# CanLogger_V2.net
KiCad netlist of a schematic drawn in EAGLE
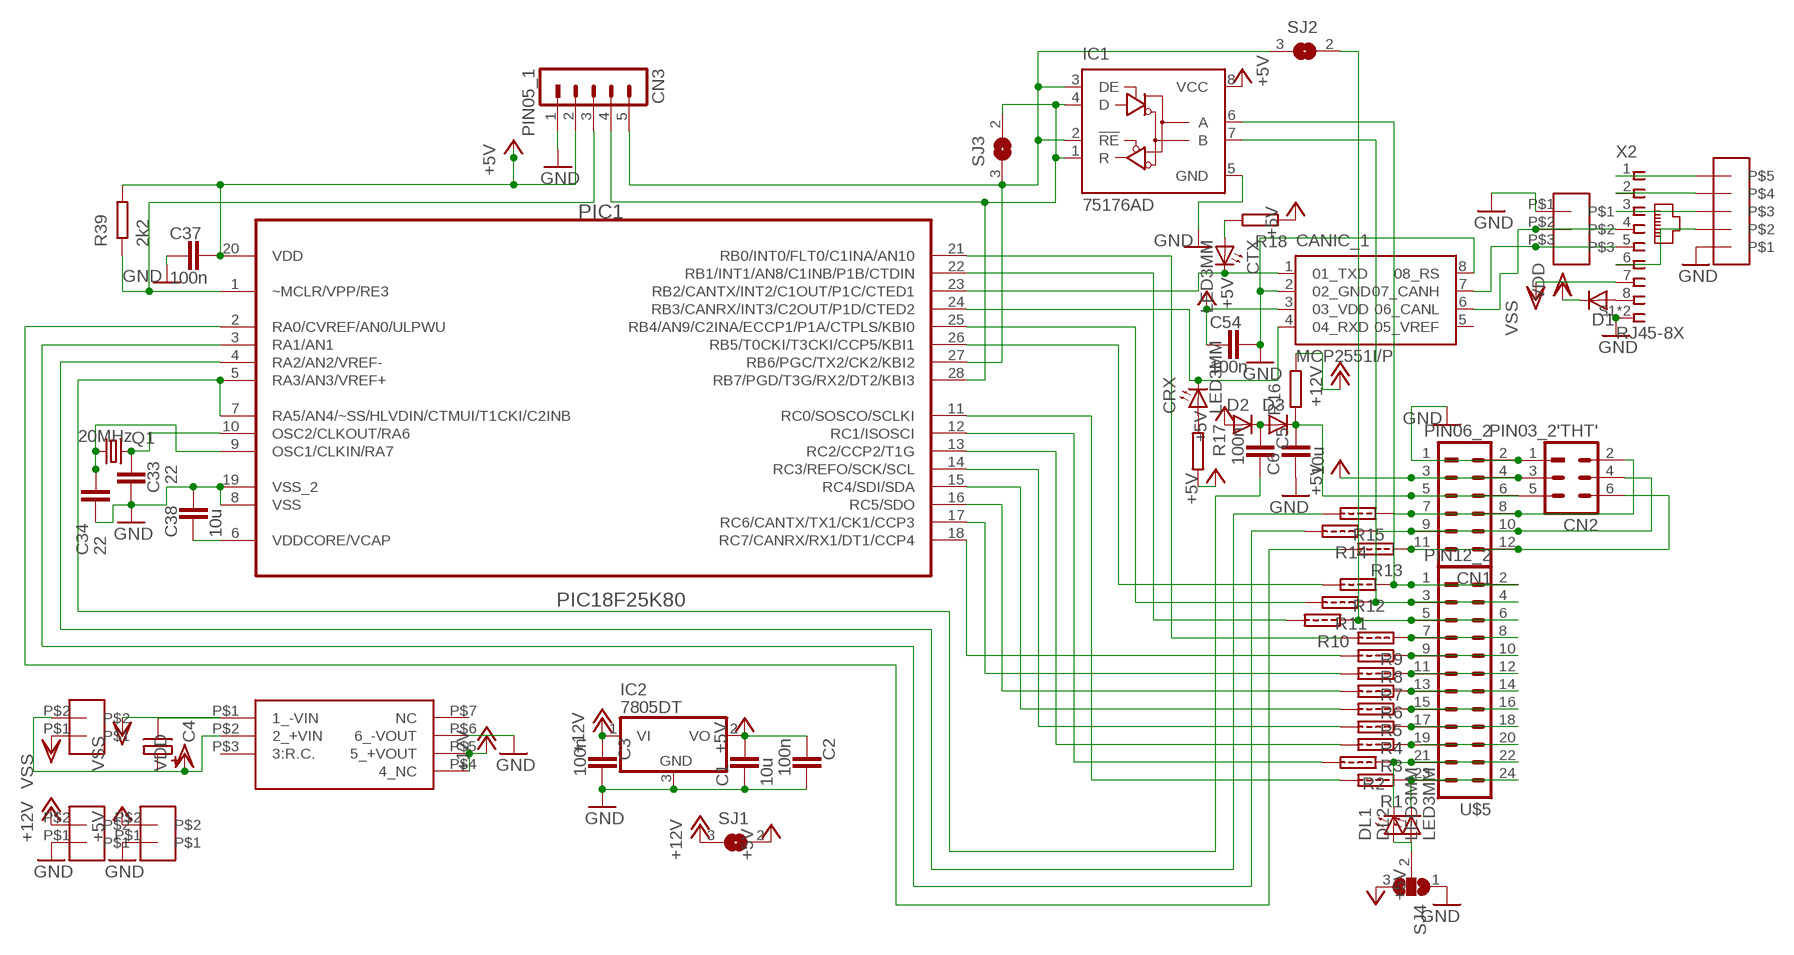
[diagram p0: schematic, sheet 1]

(export (version "E")
  (design (tool "Eeschema 10.0.6"))
  (components
    (comp (ref "C1")
      (value "10u")
      (footprint "eagle-import:R0805")
      (libsource (lib "eagle-import") (part "C0805"))
    )
    (comp (ref "C2")
      (value "100n")
      (footprint "eagle-import:R0805")
      (libsource (lib "eagle-import") (part "C0805"))
    )
    (comp (ref "C3")
      (value "100n")
      (footprint "eagle-import:R0805")
      (libsource (lib "eagle-import") (part "C0805"))
    )
    (comp (ref "C4")
      (value "C_EL1R05")
      (footprint "eagle-import:C_EL1RASZT05")
      (libsource (lib "eagle-import") (part "C_EL1R05"))
    )
    (comp (ref "C5")
      (value "100n")
      (footprint "eagle-import:R0805")
      (libsource (lib "eagle-import") (part "C0805"))
    )
    (comp (ref "C6")
      (value "10u")
      (footprint "eagle-import:R0805")
      (libsource (lib "eagle-import") (part "C0805"))
    )
    (comp (ref "C33")
      (value "22")
      (footprint "eagle-import:R0805")
      (libsource (lib "eagle-import") (part "C0805"))
    )
    (comp (ref "C34")
      (value "22")
      (footprint "eagle-import:R0805")
      (libsource (lib "eagle-import") (part "C0805"))
    )
    (comp (ref "C37")
      (value "100n")
      (footprint "eagle-import:R0805")
      (libsource (lib "eagle-import") (part "C0805"))
    )
    (comp (ref "C38")
      (value "10u")
      (footprint "eagle-import:R0805")
      (libsource (lib "eagle-import") (part "C0805"))
    )
    (comp (ref "C54")
      (value "100n")
      (footprint "eagle-import:R0805")
      (libsource (lib "eagle-import") (part "C0805"))
    )
    (comp (ref "CANIC_1")
      (value "MCP2551I/P")
      (footprint "eagle-import:DIL_8")
      (libsource (lib "eagle-import") (part "MCP2551I/P"))
    )
    (comp (ref "CN1")
      (value "PIN06_2")
      (footprint "eagle-import:PIN06_2")
      (libsource (lib "eagle-import") (part "PIN06_2"))
    )
    (comp (ref "CN2")
      (value "PIN03_2'THT'")
      (footprint "eagle-import:PIN03_2")
      (libsource (lib "eagle-import") (part "PIN03_2'THT'"))
    )
    (comp (ref "CN3")
      (value "PIN05_1")
      (footprint "eagle-import:PIN05_1")
      (libsource (lib "eagle-import") (part "PIN05_1"))
    )
    (comp (ref "CN_CAN")
      (value "FEHER_TUS_3")
      (footprint "eagle-import:FEHER_TUS_3")
      (libsource (lib "eagle-import") (part "FEHER_TUS_3"))
    )
    (comp (ref "CRX")
      (value "LED3MM")
      (footprint "eagle-import:LED3MM")
      (libsource (lib "eagle-import") (part "LED3MM"))
    )
    (comp (ref "CTX")
      (value "LED3MM")
      (footprint "eagle-import:LED3MM")
      (libsource (lib "eagle-import") (part "LED3MM"))
    )
    (comp (ref "D1")
      (value "D1R")
      (footprint "eagle-import:D1RASZT")
      (libsource (lib "eagle-import") (part "D1R"))
    )
    (comp (ref "D2")
      (value "D0805")
      (footprint "eagle-import:D0805")
      (libsource (lib "eagle-import") (part "D0805"))
    )
    (comp (ref "D3")
      (value "D0805")
      (footprint "eagle-import:D0805")
      (libsource (lib "eagle-import") (part "D0805"))
    )
    (comp (ref "DL1")
      (value "LED3MM")
      (footprint "eagle-import:LED3MM")
      (libsource (lib "eagle-import") (part "LED3MM"))
    )
    (comp (ref "DL2")
      (value "LED3MM")
      (footprint "eagle-import:LED3MM")
      (libsource (lib "eagle-import") (part "LED3MM"))
    )
    (comp (ref "IC1")
      (value "75176AD")
      (footprint "eagle-import:D_R-PDSO-G8")
      (libsource (lib "eagle-import") (part "75176AD"))
    )
    (comp (ref "IC2")
      (value "7805DT")
      (footprint "eagle-import:TO252")
      (libsource (lib "eagle-import") (part "78DT05"))
    )
    (comp (ref "PIC1")
      (value "PIC18F25K80")
      (footprint "eagle-import:SOIC127P1030X265-28N")
      (libsource (lib "eagle-import") (part "PIC18F25K80"))
    )
    (comp (ref "Q1")
      (value "20MHz")
      (footprint "eagle-import:XTAL_QS")
      (libsource (lib "eagle-import") (part "XTAL_2QS"))
    )
    (comp (ref "R1")
      (value "RNULL_EU0805")
      (footprint "eagle-import:R0805_C")
      (libsource (lib "eagle-import") (part "RNULL_EU0805"))
    )
    (comp (ref "R2")
      (value "RNULL_EU0805")
      (footprint "eagle-import:R0805_C")
      (libsource (lib "eagle-import") (part "RNULL_EU0805"))
    )
    (comp (ref "R3")
      (value "RNULL_EU0805")
      (footprint "eagle-import:R0805_C")
      (libsource (lib "eagle-import") (part "RNULL_EU0805"))
    )
    (comp (ref "R4")
      (value "RNULL_EU0805")
      (footprint "eagle-import:R0805_C")
      (libsource (lib "eagle-import") (part "RNULL_EU0805"))
    )
    (comp (ref "R5")
      (value "RNULL_EU0805")
      (footprint "eagle-import:R0805_C")
      (libsource (lib "eagle-import") (part "RNULL_EU0805"))
    )
    (comp (ref "R6")
      (value "RNULL_EU0805")
      (footprint "eagle-import:R0805_C")
      (libsource (lib "eagle-import") (part "RNULL_EU0805"))
    )
    (comp (ref "R7")
      (value "RNULL_EU0805")
      (footprint "eagle-import:R0805_C")
      (libsource (lib "eagle-import") (part "RNULL_EU0805"))
    )
    (comp (ref "R8")
      (value "RNULL_EU0805")
      (footprint "eagle-import:R0805_C")
      (libsource (lib "eagle-import") (part "RNULL_EU0805"))
    )
    (comp (ref "R9")
      (value "RNULL_EU0805")
      (footprint "eagle-import:R0805_C")
      (libsource (lib "eagle-import") (part "RNULL_EU0805"))
    )
    (comp (ref "R10")
      (value "RNULL_EU0805")
      (footprint "eagle-import:R0805_C")
      (libsource (lib "eagle-import") (part "RNULL_EU0805"))
    )
    (comp (ref "R11")
      (value "RNULL_EU0805")
      (footprint "eagle-import:R0805_C")
      (libsource (lib "eagle-import") (part "RNULL_EU0805"))
    )
    (comp (ref "R12")
      (value "RNULL_EU0805")
      (footprint "eagle-import:R0805_C")
      (libsource (lib "eagle-import") (part "RNULL_EU0805"))
    )
    (comp (ref "R13")
      (value "RNULL_EU0805")
      (footprint "eagle-import:R0805_C")
      (libsource (lib "eagle-import") (part "RNULL_EU0805"))
    )
    (comp (ref "R14")
      (value "RNULL_EU0805")
      (footprint "eagle-import:R0805_C")
      (libsource (lib "eagle-import") (part "RNULL_EU0805"))
    )
    (comp (ref "R15")
      (value "RNULL_EU0805")
      (footprint "eagle-import:R0805_C")
      (libsource (lib "eagle-import") (part "RNULL_EU0805"))
    )
    (comp (ref "R16")
      (value "R_EU0805")
      (footprint "eagle-import:R0805")
      (libsource (lib "eagle-import") (part "R_EU0805"))
    )
    (comp (ref "R17")
      (value "R_EU0805")
      (footprint "eagle-import:R0805")
      (libsource (lib "eagle-import") (part "R_EU0805"))
    )
    (comp (ref "R18")
      (value "R_EU0805")
      (footprint "eagle-import:R0805")
      (libsource (lib "eagle-import") (part "R_EU0805"))
    )
    (comp (ref "R39")
      (value "2k2")
      (footprint "eagle-import:R0805")
      (libsource (lib "eagle-import") (part "R_EU0805"))
    )
    (comp (ref "SJ1") (value "SJ") (footprint "eagle-import:SJ") (libsource (lib "eagle-import") (part "SJ")))
    (comp (ref "SJ2") (value "SJ") (footprint "eagle-import:SJ") (libsource (lib "eagle-import") (part "SJ")))
    (comp (ref "SJ3") (value "SJ") (footprint "eagle-import:SJ") (libsource (lib "eagle-import") (part "SJ")))
    (comp (ref "SJ4")
      (value "SJ2W")
      (footprint "eagle-import:SJ2")
      (libsource (lib "eagle-import") (part "SJ2W"))
    )
    (comp (ref "U$1")
      (value "FEHER_TUS_5")
      (footprint "eagle-import:FEHER_TUS_5")
      (libsource (lib "eagle-import") (part "FEHER_TUS_5"))
    )
    (comp (ref "U$2")
      (value "FEHER_TUS_2ALLO")
      (footprint "eagle-import:FEHER_TUS_2")
      (libsource (lib "eagle-import") (part "FEHER_TUS_2ALLO"))
    )
    (comp (ref "U$3")
      (value "FEHER_TUS_2ALLO")
      (footprint "eagle-import:FEHER_TUS_2")
      (libsource (lib "eagle-import") (part "FEHER_TUS_2ALLO"))
    )
    (comp (ref "U$4")
      (value "FEHER_TUS_2ALLO")
      (footprint "eagle-import:FEHER_TUS_2")
      (libsource (lib "eagle-import") (part "FEHER_TUS_2ALLO"))
    )
    (comp (ref "U$5")
      (value "PIN12_2")
      (footprint "eagle-import:PIN12_2")
      (libsource (lib "eagle-import") (part "PIN12_2"))
    )
    (comp (ref "U$6")
      (value "SPA02C")
      (footprint "eagle-import:SPA02C")
      (libsource (lib "eagle-import") (part "SPA02C"))
    )
    (comp (ref "X2")
      (value "RJ45-8X")
      (footprint "eagle-import:RJ45")
      (libsource (lib "eagle-import") (part "RJ45-8X"))
    )
  )
  (nets
    (net (code "1") (name "+5V") (class "Default")
      (node (ref "C1") (pin "1") (pinfunction "1_1") (pintype "passive"))
      (node (ref "C2") (pin "2") (pinfunction "2_2") (pintype "passive"))
      (node (ref "C37") (pin "1") (pinfunction "1_1") (pintype "passive"))
      (node (ref "C54") (pin "2") (pinfunction "2_2") (pintype "passive"))
      (node (ref "CANIC_1") (pin "3") (pinfunction "03_VDD_3") (pintype "power_in"))
      (node (ref "CN1") (pin "3") (pinfunction "3_3") (pintype "passive"))
      (node (ref "CN1") (pin "4") (pinfunction "4_4") (pintype "passive"))
      (node (ref "CN2") (pin "3") (pinfunction "3_3") (pintype "passive"))
      (node (ref "CN3") (pin "2") (pinfunction "2_2") (pintype "passive"))
      (node (ref "D2") (pin "1") (pinfunction "A_1") (pintype "passive"))
      (node (ref "IC1") (pin "8") (pinfunction "VCC_8") (pintype "power_in"))
      (node (ref "IC2") (pin "2") (pinfunction "VO_2") (pintype "passive"))
      (node (ref "PIC1") (pin "20") (pinfunction "VDD_20") (pintype "power_in"))
      (node (ref "R17") (pin "2") (pinfunction "E_2") (pintype "passive"))
      (node (ref "R18") (pin "1") (pinfunction "A_1") (pintype "passive"))
      (node (ref "R39") (pin "2") (pinfunction "E_2") (pintype "passive"))
      (node (ref "SJ1") (pin "2") (pinfunction "2_2") (pintype "passive"))
      (node (ref "SJ4") (pin "3") (pinfunction "3_3") (pintype "passive"))
      (node (ref "U$4") (pin "P$2") (pinfunction "P$2_P$2") (pintype "bidirectional"))
    )
    (net (code "2") (name "+12V") (class "Default")
      (node (ref "C3") (pin "2") (pinfunction "2_2") (pintype "passive"))
      (node (ref "IC2") (pin "1") (pinfunction "VI_1") (pintype "input"))
      (node (ref "R16") (pin "2") (pinfunction "E_2") (pintype "passive"))
      (node (ref "SJ1") (pin "3") (pinfunction "1_3") (pintype "passive"))
      (node (ref "U$3") (pin "P$2") (pinfunction "P$2_P$2") (pintype "bidirectional"))
      (node (ref "U$6") (pin "P$4") (pinfunction "4_NC_P$4") (pintype "bidirectional"))
      (node (ref "U$6") (pin "P$5") (pinfunction "5_+VOUT_P$5") (pintype "bidirectional"))
    )
    (net (code "3") (name "GND") (class "Default")
      (node (ref "C1") (pin "2") (pinfunction "2_2") (pintype "passive"))
      (node (ref "C2") (pin "1") (pinfunction "1_1") (pintype "passive"))
      (node (ref "C3") (pin "1") (pinfunction "1_1") (pintype "passive"))
      (node (ref "C33") (pin "2") (pinfunction "2_2") (pintype "passive"))
      (node (ref "C34") (pin "2") (pinfunction "2_2") (pintype "passive"))
      (node (ref "C37") (pin "2") (pinfunction "2_2") (pintype "passive"))
      (node (ref "C38") (pin "1") (pinfunction "1_1") (pintype "passive"))
      (node (ref "C54") (pin "1") (pinfunction "1_1") (pintype "passive"))
      (node (ref "C6") (pin "2") (pinfunction "2_2") (pintype "passive"))
      (node (ref "CANIC_1") (pin "2") (pinfunction "02_GND_2") (pintype "power_in"))
      (node (ref "CANIC_1") (pin "8") (pinfunction "08_RS_8") (pintype "input"))
      (node (ref "CN1") (pin "1") (pinfunction "1_1") (pintype "passive"))
      (node (ref "CN1") (pin "2") (pinfunction "2_2") (pintype "passive"))
      (node (ref "CN2") (pin "1") (pinfunction "1_1") (pintype "passive"))
      (node (ref "CN3") (pin "1") (pinfunction "1_1") (pintype "passive"))
      (node (ref "CN_CAN") (pin "P$1") (pinfunction "P$1_P$1") (pintype "bidirectional"))
      (node (ref "IC1") (pin "5") (pinfunction "GND_5") (pintype "power_in"))
      (node (ref "IC2") (pin "3") (pinfunction "GND_3") (pintype "passive"))
      (node (ref "PIC1") (pin "19") (pinfunction "VSS_2_19") (pintype "power_in"))
      (node (ref "PIC1") (pin "8") (pinfunction "VSS_8") (pintype "power_in"))
      (node (ref "SJ4") (pin "1") (pinfunction "1_1") (pintype "passive"))
      (node (ref "U$1") (pin "P$1") (pinfunction "P$1_P$1") (pintype "bidirectional"))
      (node (ref "U$3") (pin "P$1") (pinfunction "P$1_P$1") (pintype "bidirectional"))
      (node (ref "U$4") (pin "P$1") (pinfunction "P$1_P$1") (pintype "bidirectional"))
      (node (ref "U$6") (pin "P$6") (pinfunction "6_-VOUT_P$6") (pintype "bidirectional"))
      (node (ref "X2") (pin "S1") (pinfunction "S_S1") (pintype "passive"))
      (node (ref "X2") (pin "S2") (pinfunction "S_S2") (pintype "passive"))
    )
    (net (code "4") (name "Net-(CANIC_1-01_TXD)") (class "Default")
      (node (ref "CANIC_1") (pin "1") (pinfunction "01_TXD_1") (pintype "input"))
      (node (ref "CTX") (pin "K") (pinfunction "C_K") (pintype "passive"))
      (node (ref "PIC1") (pin "23") (pinfunction "RB2/CANTX/INT2/C1OUT/P1C/CTED1_23") (pintype "bidirectional"))
    )
    (net (code "5") (name "Net-(CANIC_1-04_RXD)") (class "Default")
      (node (ref "CANIC_1") (pin "4") (pinfunction "04_RXD_4") (pintype "output"))
      (node (ref "CRX") (pin "K") (pinfunction "C_K") (pintype "passive"))
      (node (ref "PIC1") (pin "24") (pinfunction "RB3/CANRX/INT3/C2OUT/P1D/CTED2_24") (pintype "bidirectional"))
    )
    (net (code "6") (name "Net-(CANIC_1-06_CANL)") (class "Default")
      (node (ref "CANIC_1") (pin "6") (pinfunction "06_CANL_6") (pintype "bidirectional"))
      (node (ref "CN_CAN") (pin "P$2") (pinfunction "P$2_P$2") (pintype "bidirectional"))
      (node (ref "X2") (pin "4") (pinfunction "4_4") (pintype "passive"))
    )
    (net (code "7") (name "Net-(CANIC_1-07_CANH)") (class "Default")
      (node (ref "CANIC_1") (pin "7") (pinfunction "07_CANH_7") (pintype "bidirectional"))
      (node (ref "CN_CAN") (pin "P$3") (pinfunction "P$3_P$3") (pintype "bidirectional"))
      (node (ref "X2") (pin "5") (pinfunction "5_5") (pintype "passive"))
    )
    (net (code "8") (name "Net-(D1-A)") (class "Default")
      (node (ref "D1") (pin "P$1") (pinfunction "A_P$1") (pintype "passive"))
      (node (ref "X2") (pin "8") (pinfunction "8_8") (pintype "passive"))
    )
    (net (code "9") (name "Net-(D2-C)") (class "Default")
      (node (ref "C5") (pin "2") (pinfunction "2_2") (pintype "passive"))
      (node (ref "D2") (pin "2") (pinfunction "C_2") (pintype "passive"))
      (node (ref "D3") (pin "1") (pinfunction "A_1") (pintype "passive"))
    )
    (net (code "10") (name "Net-(D3-C)") (class "Default")
      (node (ref "C6") (pin "1") (pinfunction "1_1") (pintype "passive"))
      (node (ref "CN1") (pin "5") (pinfunction "5_5") (pintype "passive"))
      (node (ref "CN1") (pin "6") (pinfunction "6_6") (pintype "passive"))
      (node (ref "CN2") (pin "5") (pinfunction "5_5") (pintype "passive"))
      (node (ref "D3") (pin "2") (pinfunction "C_2") (pintype "passive"))
      (node (ref "R16") (pin "1") (pinfunction "A_1") (pintype "passive"))
    )
    (net (code "11") (name "Net-(DL1-C)") (class "Default")
      (node (ref "DL1") (pin "K") (pinfunction "C_K") (pintype "passive"))
      (node (ref "R2") (pin "1") (pinfunction "A_1") (pintype "passive"))
      (node (ref "U$5") (pin "21") (pinfunction "21_21") (pintype "passive"))
      (node (ref "U$5") (pin "22") (pinfunction "22_22") (pintype "passive"))
    )
    (net (code "12") (name "Net-(DL1-PadA)") (class "Default")
      (node (ref "DL1") (pin "A") (pinfunction "A_A") (pintype "passive"))
      (node (ref "DL2") (pin "A") (pinfunction "A_A") (pintype "passive"))
      (node (ref "SJ4") (pin "2") (pinfunction "2_2") (pintype "passive"))
    )
    (net (code "13") (name "Net-(DL2-C)") (class "Default")
      (node (ref "DL2") (pin "K") (pinfunction "C_K") (pintype "passive"))
      (node (ref "R1") (pin "1") (pinfunction "A_1") (pintype "passive"))
      (node (ref "U$5") (pin "23") (pinfunction "23_23") (pintype "passive"))
      (node (ref "U$5") (pin "24") (pinfunction "24_24") (pintype "passive"))
    )
    (net (code "14") (name "Net-(IC1-A)") (class "Default")
      (node (ref "IC1") (pin "6") (pinfunction "A_6") (pintype "output"))
      (node (ref "R12") (pin "1") (pinfunction "A_1") (pintype "passive"))
      (node (ref "U$5") (pin "1") (pinfunction "1_1") (pintype "passive"))
      (node (ref "U$5") (pin "2") (pinfunction "2_2") (pintype "passive"))
    )
    (net (code "15") (name "Net-(IC1-B)") (class "Default")
      (node (ref "IC1") (pin "7") (pinfunction "B_7") (pintype "output"))
      (node (ref "R11") (pin "1") (pinfunction "A_1") (pintype "passive"))
      (node (ref "U$5") (pin "3") (pinfunction "3_3") (pintype "passive"))
      (node (ref "U$5") (pin "4") (pinfunction "4_4") (pintype "passive"))
    )
    (net (code "16") (name "Net-(IC1-D)") (class "Default")
      (node (ref "CN3") (pin "4") (pinfunction "4_4") (pintype "passive"))
      (node (ref "IC1") (pin "1") (pinfunction "R_1") (pintype "input"))
      (node (ref "IC1") (pin "4") (pinfunction "D_4") (pintype "input"))
      (node (ref "PIC1") (pin "28") (pinfunction "RB7/PGD/T3G/RX2/DT2/KBI3_28") (pintype "bidirectional"))
      (node (ref "SJ3") (pin "2") (pinfunction "2_2") (pintype "passive"))
    )
    (net (code "17") (name "Net-(IC1-DE)") (class "Default")
      (node (ref "CN3") (pin "5") (pinfunction "5_5") (pintype "passive"))
      (node (ref "IC1") (pin "2") (pinfunction "~{RE}_2") (pintype "input"))
      (node (ref "IC1") (pin "3") (pinfunction "DE_3") (pintype "input"))
      (node (ref "PIC1") (pin "27") (pinfunction "RB6/PGC/TX2/CK2/KBI2_27") (pintype "bidirectional"))
      (node (ref "SJ2") (pin "3") (pinfunction "1_3") (pintype "passive"))
      (node (ref "SJ3") (pin "3") (pinfunction "1_3") (pintype "passive"))
    )
    (net (code "18") (name "Net-(PIC1-OSC1{slash}CLKIN{slash}RA7)") (class "Default")
      (node (ref "C34") (pin "1") (pinfunction "1_1") (pintype "passive"))
      (node (ref "PIC1") (pin "9") (pinfunction "OSC1/CLKIN/RA7_9") (pintype "bidirectional"))
      (node (ref "Q1") (pin "1") (pinfunction "1_1") (pintype "passive"))
    )
    (net (code "19") (name "Net-(PIC1-OSC2{slash}CLKOUT{slash}RA6)") (class "Default")
      (node (ref "C33") (pin "1") (pinfunction "1_1") (pintype "passive"))
      (node (ref "PIC1") (pin "10") (pinfunction "OSC2/CLKOUT/RA6_10") (pintype "bidirectional"))
      (node (ref "Q1") (pin "2") (pinfunction "2_2") (pintype "passive"))
    )
    (net (code "20") (name "Net-(PIC1-RA0{slash}CVREF{slash}AN0{slash}ULPWU)") (class "Default")
      (node (ref "PIC1") (pin "2") (pinfunction "RA0/CVREF/AN0/ULPWU_2") (pintype "bidirectional"))
      (node (ref "R13") (pin "2") (pinfunction "E_2") (pintype "passive"))
    )
    (net (code "21") (name "Net-(PIC1-RA1{slash}AN1)") (class "Default")
      (node (ref "PIC1") (pin "3") (pinfunction "RA1/AN1_3") (pintype "bidirectional"))
      (node (ref "R14") (pin "2") (pinfunction "E_2") (pintype "passive"))
    )
    (net (code "22") (name "Net-(PIC1-RA2{slash}AN2{slash}VREF-)") (class "Default")
      (node (ref "PIC1") (pin "4") (pinfunction "RA2/AN2/VREF-_4") (pintype "bidirectional"))
      (node (ref "R15") (pin "2") (pinfunction "E_2") (pintype "passive"))
    )
    (net (code "23") (name "Net-(PIC1-RA3{slash}AN3{slash}VREF+)") (class "Default")
      (node (ref "C5") (pin "1") (pinfunction "1_1") (pintype "passive"))
      (node (ref "PIC1") (pin "5") (pinfunction "RA3/AN3/VREF+_5") (pintype "bidirectional"))
      (node (ref "PIC1") (pin "7") (pinfunction "RA5/AN4/~{SS/HLVDIN/CTMUI/T1CKI/C2INB}_7") (pintype "bidirectional"))
    )
    (net (code "24") (name "Net-(PIC1-RB0{slash}INT0{slash}FLT0{slash}C1INA{slash}AN10)") (class "Default")
      (node (ref "PIC1") (pin "21") (pinfunction "RB0/INT0/FLT0/C1INA/AN10_21") (pintype "bidirectional"))
      (node (ref "R9") (pin "2") (pinfunction "E_2") (pintype "passive"))
    )
    (net (code "25") (name "Net-(PIC1-RB1{slash}INT1{slash}AN8{slash}C1INB{slash}P1B{slash}CTDIN)") (class "Default")
      (node (ref "PIC1") (pin "22") (pinfunction "RB1/INT1/AN8/C1INB/P1B/CTDIN_22") (pintype "bidirectional"))
      (node (ref "R10") (pin "2") (pinfunction "E_2") (pintype "passive"))
    )
    (net (code "26") (name "Net-(PIC1-RB4{slash}AN9{slash}C2INA{slash}ECCP1{slash}P1A{slash}CTPLS{slash}KBI0)") (class "Default")
      (node (ref "PIC1") (pin "25") (pinfunction "RB4/AN9/C2INA/ECCP1/P1A/CTPLS/KBI0_25") (pintype "bidirectional"))
      (node (ref "R11") (pin "2") (pinfunction "E_2") (pintype "passive"))
    )
    (net (code "27") (name "Net-(PIC1-RB5{slash}T0CKI{slash}T3CKI{slash}CCP5{slash}KBI1)") (class "Default")
      (node (ref "PIC1") (pin "26") (pinfunction "RB5/T0CKI/T3CKI/CCP5/KBI1_26") (pintype "bidirectional"))
      (node (ref "R12") (pin "2") (pinfunction "E_2") (pintype "passive"))
    )
    (net (code "28") (name "Net-(PIC1-RC0{slash}SOSCO{slash}SCLKI)") (class "Default")
      (node (ref "PIC1") (pin "11") (pinfunction "RC0/SOSCO/SCLKI_11") (pintype "bidirectional"))
      (node (ref "R1") (pin "2") (pinfunction "E_2") (pintype "passive"))
    )
    (net (code "29") (name "Net-(PIC1-RC1{slash}ISOSCI)") (class "Default")
      (node (ref "PIC1") (pin "12") (pinfunction "RC1/ISOSCI_12") (pintype "bidirectional"))
      (node (ref "R2") (pin "2") (pinfunction "E_2") (pintype "passive"))
    )
    (net (code "30") (name "Net-(PIC1-RC2{slash}CCP2{slash}T1G)") (class "Default")
      (node (ref "PIC1") (pin "13") (pinfunction "RC2/CCP2/T1G_13") (pintype "bidirectional"))
      (node (ref "R3") (pin "2") (pinfunction "E_2") (pintype "passive"))
    )
    (net (code "31") (name "Net-(PIC1-RC3{slash}REFO{slash}SCK{slash}SCL)") (class "Default")
      (node (ref "PIC1") (pin "14") (pinfunction "RC3/REFO/SCK/SCL_14") (pintype "bidirectional"))
      (node (ref "R4") (pin "2") (pinfunction "E_2") (pintype "passive"))
    )
    (net (code "32") (name "Net-(PIC1-RC4{slash}SDI{slash}SDA)") (class "Default")
      (node (ref "PIC1") (pin "15") (pinfunction "RC4/SDI/SDA_15") (pintype "bidirectional"))
      (node (ref "R5") (pin "2") (pinfunction "E_2") (pintype "passive"))
    )
    (net (code "33") (name "Net-(PIC1-RC5{slash}SDO)") (class "Default")
      (node (ref "PIC1") (pin "16") (pinfunction "RC5/SDO_16") (pintype "bidirectional"))
      (node (ref "R6") (pin "2") (pinfunction "E_2") (pintype "passive"))
    )
    (net (code "34") (name "Net-(PIC1-RC6{slash}CANTX{slash}TX1{slash}CK1{slash}CCP3)") (class "Default")
      (node (ref "PIC1") (pin "17") (pinfunction "RC6/CANTX/TX1/CK1/CCP3_17") (pintype "bidirectional"))
      (node (ref "R7") (pin "2") (pinfunction "E_2") (pintype "passive"))
    )
    (net (code "35") (name "Net-(PIC1-RC7{slash}CANRX{slash}RX1{slash}DT1{slash}CCP4)") (class "Default")
      (node (ref "PIC1") (pin "18") (pinfunction "RC7/CANRX/RX1/DT1/CCP4_18") (pintype "bidirectional"))
      (node (ref "R8") (pin "2") (pinfunction "E_2") (pintype "passive"))
    )
    (net (code "36") (name "Net-(PIC1-VDDCORE{slash}VCAP)") (class "Default")
      (node (ref "C38") (pin "2") (pinfunction "2_2") (pintype "passive"))
      (node (ref "PIC1") (pin "6") (pinfunction "VDDCORE/VCAP_6") (pintype "bidirectional"))
    )
    (net (code "37") (name "Net-(PIC1-~{MCLR{slash}VPP{slash}RE3})") (class "Default")
      (node (ref "CN3") (pin "3") (pinfunction "3_3") (pintype "passive"))
      (node (ref "PIC1") (pin "1") (pinfunction "~{MCLR/VPP/RE3}_1") (pintype "input"))
      (node (ref "R39") (pin "1") (pinfunction "A_1") (pintype "passive"))
    )
    (net (code "38") (name "Net-(R3-A)") (class "Default")
      (node (ref "R3") (pin "1") (pinfunction "A_1") (pintype "passive"))
      (node (ref "U$5") (pin "19") (pinfunction "19_19") (pintype "passive"))
    )
    (net (code "39") (name "Net-(R4-A)") (class "Default")
      (node (ref "R4") (pin "1") (pinfunction "A_1") (pintype "passive"))
      (node (ref "U$5") (pin "17") (pinfunction "17_17") (pintype "passive"))
      (node (ref "U$5") (pin "18") (pinfunction "18_18") (pintype "passive"))
    )
    (net (code "40") (name "Net-(R5-A)") (class "Default")
      (node (ref "R5") (pin "1") (pinfunction "A_1") (pintype "passive"))
      (node (ref "U$5") (pin "15") (pinfunction "15_15") (pintype "passive"))
      (node (ref "U$5") (pin "16") (pinfunction "16_16") (pintype "passive"))
    )
    (net (code "41") (name "Net-(R6-A)") (class "Default")
      (node (ref "R6") (pin "1") (pinfunction "A_1") (pintype "passive"))
      (node (ref "U$5") (pin "13") (pinfunction "13_13") (pintype "passive"))
      (node (ref "U$5") (pin "14") (pinfunction "14_14") (pintype "passive"))
    )
    (net (code "42") (name "Net-(R7-A)") (class "Default")
      (node (ref "R7") (pin "1") (pinfunction "A_1") (pintype "passive"))
      (node (ref "U$5") (pin "11") (pinfunction "11_11") (pintype "passive"))
      (node (ref "U$5") (pin "12") (pinfunction "12_12") (pintype "passive"))
    )
    (net (code "43") (name "Net-(R8-A)") (class "Default")
      (node (ref "R8") (pin "1") (pinfunction "A_1") (pintype "passive"))
      (node (ref "U$5") (pin "10") (pinfunction "10_10") (pintype "passive"))
      (node (ref "U$5") (pin "9") (pinfunction "9_9") (pintype "passive"))
    )
    (net (code "44") (name "Net-(R9-A)") (class "Default")
      (node (ref "R9") (pin "1") (pinfunction "A_1") (pintype "passive"))
      (node (ref "U$5") (pin "7") (pinfunction "7_7") (pintype "passive"))
      (node (ref "U$5") (pin "8") (pinfunction "8_8") (pintype "passive"))
    )
    (net (code "45") (name "Net-(R10-A)") (class "Default")
      (node (ref "R10") (pin "1") (pinfunction "A_1") (pintype "passive"))
      (node (ref "SJ2") (pin "2") (pinfunction "2_2") (pintype "passive"))
      (node (ref "U$5") (pin "5") (pinfunction "5_5") (pintype "passive"))
      (node (ref "U$5") (pin "6") (pinfunction "6_6") (pintype "passive"))
    )
    (net (code "46") (name "Net-(R13-A)") (class "Default")
      (node (ref "CN1") (pin "11") (pinfunction "11_11") (pintype "passive"))
      (node (ref "CN1") (pin "12") (pinfunction "12_12") (pintype "passive"))
      (node (ref "CN2") (pin "6") (pinfunction "6_6") (pintype "passive"))
      (node (ref "R13") (pin "1") (pinfunction "A_1") (pintype "passive"))
    )
    (net (code "47") (name "Net-(R14-A)") (class "Default")
      (node (ref "CN1") (pin "10") (pinfunction "10_10") (pintype "passive"))
      (node (ref "CN1") (pin "9") (pinfunction "9_9") (pintype "passive"))
      (node (ref "CN2") (pin "4") (pinfunction "4_4") (pintype "passive"))
      (node (ref "R14") (pin "1") (pinfunction "A_1") (pintype "passive"))
    )
    (net (code "48") (name "Net-(R15-A)") (class "Default")
      (node (ref "CN1") (pin "7") (pinfunction "7_7") (pintype "passive"))
      (node (ref "CN1") (pin "8") (pinfunction "8_8") (pintype "passive"))
      (node (ref "CN2") (pin "2") (pinfunction "2_2") (pintype "passive"))
      (node (ref "R15") (pin "1") (pinfunction "A_1") (pintype "passive"))
    )
    (net (code "49") (name "Net-(R17-A)") (class "Default")
      (node (ref "CRX") (pin "A") (pinfunction "A_A") (pintype "passive"))
      (node (ref "R17") (pin "1") (pinfunction "A_1") (pintype "passive"))
    )
    (net (code "50") (name "Net-(R18-E)") (class "Default")
      (node (ref "CTX") (pin "A") (pinfunction "A_A") (pintype "passive"))
      (node (ref "R18") (pin "2") (pinfunction "E_2") (pintype "passive"))
    )
    (net (code "51") (name "Net-(U$1-PadP$2)") (class "Default")
      (node (ref "U$1") (pin "P$2") (pinfunction "P$2_P$2") (pintype "bidirectional"))
      (node (ref "X2") (pin "6") (pinfunction "6_6") (pintype "passive"))
    )
    (net (code "52") (name "Net-(U$1-PadP$3)") (class "Default")
      (node (ref "U$1") (pin "P$3") (pinfunction "P$3_P$3") (pintype "bidirectional"))
      (node (ref "X2") (pin "3") (pinfunction "3_3") (pintype "passive"))
    )
    (net (code "53") (name "Net-(U$1-PadP$4)") (class "Default")
      (node (ref "U$1") (pin "P$4") (pinfunction "P$4_P$4") (pintype "bidirectional"))
      (node (ref "X2") (pin "2") (pinfunction "2_2") (pintype "passive"))
    )
    (net (code "54") (name "Net-(U$1-PadP$5)") (class "Default")
      (node (ref "U$1") (pin "P$5") (pinfunction "P$5_P$5") (pintype "bidirectional"))
      (node (ref "X2") (pin "1") (pinfunction "1_1") (pintype "passive"))
    )
    (net (code "55") (name "VDD") (class "Default")
      (node (ref "C4") (pin "P+") (pinfunction "P+_P+") (pintype "passive"))
      (node (ref "D1") (pin "P$2") (pinfunction "C_P$2") (pintype "passive"))
      (node (ref "U$2") (pin "P$2") (pinfunction "P$2_P$2") (pintype "bidirectional"))
      (node (ref "U$6") (pin "P$2") (pinfunction "2_+VIN_P$2") (pintype "bidirectional"))
    )
    (net (code "56") (name "VSS") (class "Default")
      (node (ref "C4") (pin "P-") (pinfunction "P-_P-") (pintype "passive"))
      (node (ref "U$2") (pin "P$1") (pinfunction "P$1_P$1") (pintype "bidirectional"))
      (node (ref "U$6") (pin "P$1") (pinfunction "1_-VIN_P$1") (pintype "bidirectional"))
      (node (ref "X2") (pin "7") (pinfunction "7_7") (pintype "passive"))
    )
    (net (code "57") (name "unconnected-(CANIC_1-05_VREF-Pad5)") (class "Default")
      (node (ref "CANIC_1") (pin "5") (pinfunction "05_VREF_5") (pintype "input"))
    )
    (net (code "58") (name "unconnected-(U$5-Pad20)") (class "Default")
      (node (ref "U$5") (pin "20") (pinfunction "20_20") (pintype "passive"))
    )
    (net (code "59") (name "unconnected-(U$6-3:R.C.-PadP$3)") (class "Default")
      (node (ref "U$6") (pin "P$3") (pinfunction "3:R.C._P$3") (pintype "bidirectional"))
    )
    (net (code "60") (name "unconnected-(U$6-NC-PadP$7)") (class "Default")
      (node (ref "U$6") (pin "P$7") (pinfunction "NC_P$7") (pintype "bidirectional"))
    )
  )
)
